# R-breakout.net
KiCad netlist of a schematic drawn in EAGLE
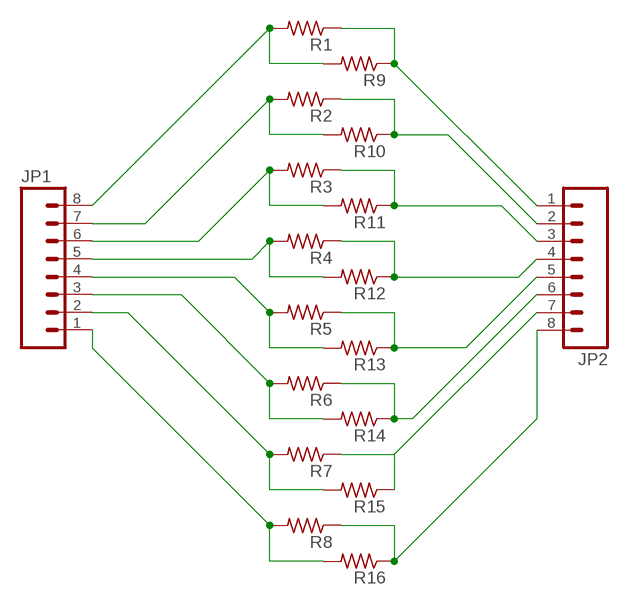
[diagram p0: schematic, sheet 1]

(export (version "E")
  (design (tool "Eeschema 10.0.6"))
  (components
    (comp (ref "JP1")
      (value "M081X08")
      (footprint "eagle-import:1X08")
      (libsource (lib "eagle-import") (part "M081X08"))
    )
    (comp (ref "JP2")
      (value "M081X08")
      (footprint "eagle-import:1X08")
      (libsource (lib "eagle-import") (part "M081X08"))
    )
    (comp (ref "R1")
      (value "RESISTORR0805")
      (footprint "eagle-import:R0805")
      (libsource (lib "eagle-import") (part "RESISTORR0805"))
    )
    (comp (ref "R2")
      (value "RESISTORR0805")
      (footprint "eagle-import:R0805")
      (libsource (lib "eagle-import") (part "RESISTORR0805"))
    )
    (comp (ref "R3")
      (value "RESISTORR0805")
      (footprint "eagle-import:R0805")
      (libsource (lib "eagle-import") (part "RESISTORR0805"))
    )
    (comp (ref "R4")
      (value "RESISTORR0805")
      (footprint "eagle-import:R0805")
      (libsource (lib "eagle-import") (part "RESISTORR0805"))
    )
    (comp (ref "R5")
      (value "RESISTORR0805")
      (footprint "eagle-import:R0805")
      (libsource (lib "eagle-import") (part "RESISTORR0805"))
    )
    (comp (ref "R6")
      (value "RESISTORR0805")
      (footprint "eagle-import:R0805")
      (libsource (lib "eagle-import") (part "RESISTORR0805"))
    )
    (comp (ref "R7")
      (value "RESISTORR0805")
      (footprint "eagle-import:R0805")
      (libsource (lib "eagle-import") (part "RESISTORR0805"))
    )
    (comp (ref "R8")
      (value "RESISTORR0805")
      (footprint "eagle-import:R0805")
      (libsource (lib "eagle-import") (part "RESISTORR0805"))
    )
    (comp (ref "R9")
      (value "RESISTORR1206")
      (footprint "eagle-import:R1206")
      (libsource (lib "eagle-import") (part "RESISTORR1206"))
    )
    (comp (ref "R10")
      (value "RESISTORR1206")
      (footprint "eagle-import:R1206")
      (libsource (lib "eagle-import") (part "RESISTORR1206"))
    )
    (comp (ref "R11")
      (value "RESISTORR1206")
      (footprint "eagle-import:R1206")
      (libsource (lib "eagle-import") (part "RESISTORR1206"))
    )
    (comp (ref "R12")
      (value "RESISTORR1206")
      (footprint "eagle-import:R1206")
      (libsource (lib "eagle-import") (part "RESISTORR1206"))
    )
    (comp (ref "R13")
      (value "RESISTORR1206")
      (footprint "eagle-import:R1206")
      (libsource (lib "eagle-import") (part "RESISTORR1206"))
    )
    (comp (ref "R14")
      (value "RESISTORR1206")
      (footprint "eagle-import:R1206")
      (libsource (lib "eagle-import") (part "RESISTORR1206"))
    )
    (comp (ref "R15")
      (value "RESISTORR1206")
      (footprint "eagle-import:R1206")
      (libsource (lib "eagle-import") (part "RESISTORR1206"))
    )
    (comp (ref "R16")
      (value "RESISTORR1206")
      (footprint "eagle-import:R1206")
      (libsource (lib "eagle-import") (part "RESISTORR1206"))
    )
  )
  (nets
    (net (code "1") (name "Net-(JP1-Pad1)") (class "Default")
      (node (ref "JP1") (pin "1") (pinfunction "1_1") (pintype "passive"))
      (node (ref "R16") (pin "2") (pinfunction "2_2") (pintype "passive"))
      (node (ref "R8") (pin "2") (pinfunction "2_2") (pintype "passive"))
    )
    (net (code "2") (name "Net-(JP1-Pad2)") (class "Default")
      (node (ref "JP1") (pin "2") (pinfunction "2_2") (pintype "passive"))
      (node (ref "R15") (pin "2") (pinfunction "2_2") (pintype "passive"))
      (node (ref "R7") (pin "2") (pinfunction "2_2") (pintype "passive"))
    )
    (net (code "3") (name "Net-(JP1-Pad3)") (class "Default")
      (node (ref "JP1") (pin "3") (pinfunction "3_3") (pintype "passive"))
      (node (ref "R14") (pin "2") (pinfunction "2_2") (pintype "passive"))
      (node (ref "R6") (pin "2") (pinfunction "2_2") (pintype "passive"))
    )
    (net (code "4") (name "Net-(JP1-Pad4)") (class "Default")
      (node (ref "JP1") (pin "4") (pinfunction "4_4") (pintype "passive"))
      (node (ref "R13") (pin "2") (pinfunction "2_2") (pintype "passive"))
      (node (ref "R5") (pin "2") (pinfunction "2_2") (pintype "passive"))
    )
    (net (code "5") (name "Net-(JP1-Pad5)") (class "Default")
      (node (ref "JP1") (pin "5") (pinfunction "5_5") (pintype "passive"))
      (node (ref "R12") (pin "2") (pinfunction "2_2") (pintype "passive"))
      (node (ref "R4") (pin "2") (pinfunction "2_2") (pintype "passive"))
    )
    (net (code "6") (name "Net-(JP1-Pad6)") (class "Default")
      (node (ref "JP1") (pin "6") (pinfunction "6_6") (pintype "passive"))
      (node (ref "R11") (pin "2") (pinfunction "2_2") (pintype "passive"))
      (node (ref "R3") (pin "2") (pinfunction "2_2") (pintype "passive"))
    )
    (net (code "7") (name "Net-(JP1-Pad7)") (class "Default")
      (node (ref "JP1") (pin "7") (pinfunction "7_7") (pintype "passive"))
      (node (ref "R10") (pin "2") (pinfunction "2_2") (pintype "passive"))
      (node (ref "R2") (pin "2") (pinfunction "2_2") (pintype "passive"))
    )
    (net (code "8") (name "Net-(JP1-Pad8)") (class "Default")
      (node (ref "JP1") (pin "8") (pinfunction "8_8") (pintype "passive"))
      (node (ref "R1") (pin "2") (pinfunction "2_2") (pintype "passive"))
      (node (ref "R9") (pin "2") (pinfunction "2_2") (pintype "passive"))
    )
    (net (code "9") (name "Net-(JP2-Pad1)") (class "Default")
      (node (ref "JP2") (pin "1") (pinfunction "1_1") (pintype "passive"))
      (node (ref "R1") (pin "1") (pinfunction "1_1") (pintype "passive"))
      (node (ref "R9") (pin "1") (pinfunction "1_1") (pintype "passive"))
    )
    (net (code "10") (name "Net-(JP2-Pad2)") (class "Default")
      (node (ref "JP2") (pin "2") (pinfunction "2_2") (pintype "passive"))
      (node (ref "R10") (pin "1") (pinfunction "1_1") (pintype "passive"))
      (node (ref "R2") (pin "1") (pinfunction "1_1") (pintype "passive"))
    )
    (net (code "11") (name "Net-(JP2-Pad3)") (class "Default")
      (node (ref "JP2") (pin "3") (pinfunction "3_3") (pintype "passive"))
      (node (ref "R11") (pin "1") (pinfunction "1_1") (pintype "passive"))
      (node (ref "R3") (pin "1") (pinfunction "1_1") (pintype "passive"))
    )
    (net (code "12") (name "Net-(JP2-Pad4)") (class "Default")
      (node (ref "JP2") (pin "4") (pinfunction "4_4") (pintype "passive"))
      (node (ref "R12") (pin "1") (pinfunction "1_1") (pintype "passive"))
      (node (ref "R4") (pin "1") (pinfunction "1_1") (pintype "passive"))
    )
    (net (code "13") (name "Net-(JP2-Pad5)") (class "Default")
      (node (ref "JP2") (pin "5") (pinfunction "5_5") (pintype "passive"))
      (node (ref "R13") (pin "1") (pinfunction "1_1") (pintype "passive"))
      (node (ref "R5") (pin "1") (pinfunction "1_1") (pintype "passive"))
    )
    (net (code "14") (name "Net-(JP2-Pad6)") (class "Default")
      (node (ref "JP2") (pin "6") (pinfunction "6_6") (pintype "passive"))
      (node (ref "R14") (pin "1") (pinfunction "1_1") (pintype "passive"))
      (node (ref "R6") (pin "1") (pinfunction "1_1") (pintype "passive"))
    )
    (net (code "15") (name "Net-(JP2-Pad7)") (class "Default")
      (node (ref "JP2") (pin "7") (pinfunction "7_7") (pintype "passive"))
      (node (ref "R15") (pin "1") (pinfunction "1_1") (pintype "passive"))
      (node (ref "R7") (pin "1") (pinfunction "1_1") (pintype "passive"))
    )
    (net (code "16") (name "Net-(JP2-Pad8)") (class "Default")
      (node (ref "JP2") (pin "8") (pinfunction "8_8") (pintype "passive"))
      (node (ref "R16") (pin "1") (pinfunction "1_1") (pintype "passive"))
      (node (ref "R8") (pin "1") (pinfunction "1_1") (pintype "passive"))
    )
  )
)
